# BLDC_DRIVER_REUSEPhase.net
KiCad netlist of a schematic drawn in EasyEDA Pro
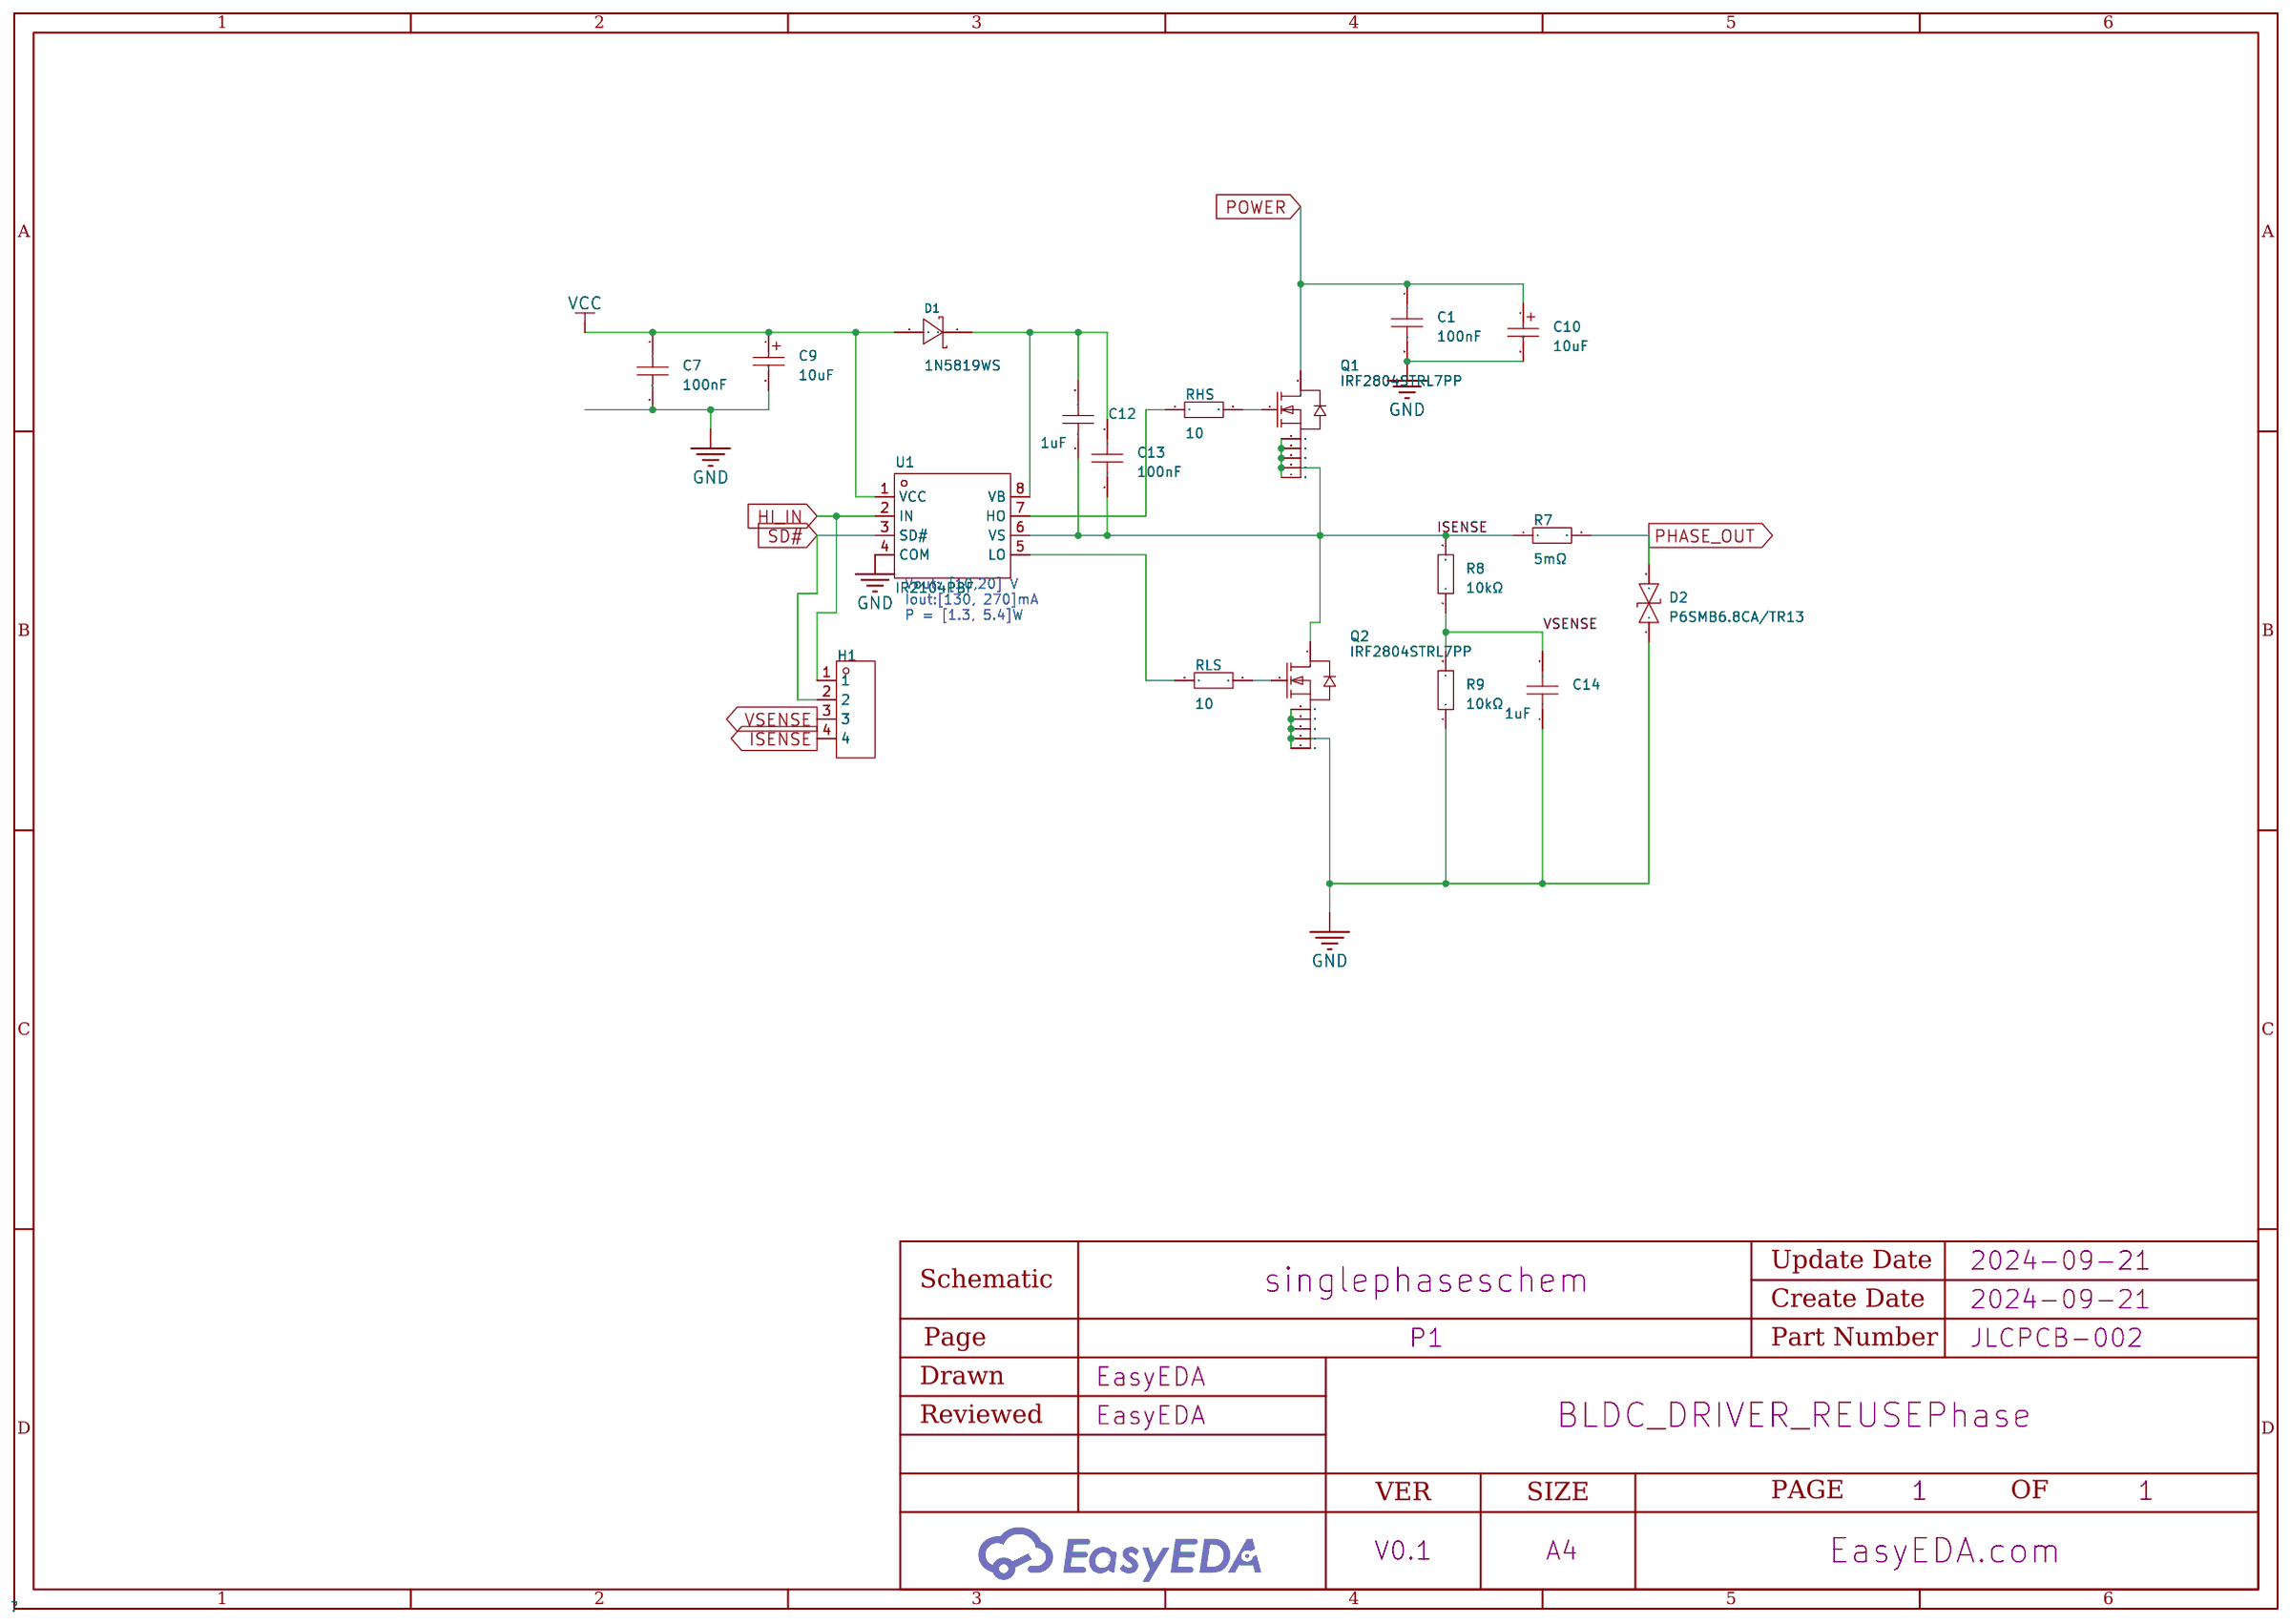
[diagram p0: schematic sheet]

(export (version "E")
  (design (tool "Eeschema 10.0.6"))
  (components
    (comp (ref "C1")
      (value "100nF")
      (footprint "easyedapro:C0603")
      (libsource (lib "easyedapro") (part "CAP"))
    )
    (comp (ref "C7")
      (value "100nF")
      (footprint "easyedapro:C0603")
      (libsource (lib "easyedapro") (part "CAP"))
    )
    (comp (ref "C9")
      (value "10uF")
      (footprint "easyedapro:CAP-SMD_BD5.0-L5.3-W5.3-LS6.3-FD")
      (libsource (lib "easyedapro") (part "C_Ele_SMD"))
    )
    (comp (ref "C10")
      (value "10uF")
      (footprint "easyedapro:CAP-SMD_BD5.0-L5.3-W5.3-LS6.3-FD")
      (libsource (lib "easyedapro") (part "C_Ele_SMD"))
    )
    (comp (ref "C12")
      (value "1uF")
      (footprint "easyedapro:CAP-TH_L7.2-W2.5-P5.00-D0.6")
      (fields (field (name "Manufacturer Part") "SMEC334J100M2") (field (name "Manufacturer") "CHAMPION(全鹏)"))
      (libsource (lib "easyedapro") (part "SMEC334J100M2"))
    )
    (comp (ref "C13")
      (value "100nF")
      (footprint "easyedapro:C0603")
      (libsource (lib "easyedapro") (part "CAP"))
    )
    (comp (ref "C14")
      (value "1uF")
      (footprint "easyedapro:CAP-TH_L7.2-W2.5-P5.00-D0.6")
      (fields (field (name "Manufacturer Part") "SMEC334J100M2") (field (name "Manufacturer") "CHAMPION(全鹏)"))
      (libsource (lib "easyedapro") (part "SMEC334J100M2"))
    )
    (comp (ref "D1")
      (value "1N5819WS")
      (footprint "easyedapro:SOD-323_L1.8-W1.3-LS2.5-RD")
      (description "Forward Voltage (Vf@If):600mV@1A Reverse Voltage (Vr):40V Average Rectified Current (Io):1A")
      (fields (field (name "Manufacturer") "Hottech(合科泰)"))
      (libsource (lib "easyedapro") (part "1N5819WS"))
    )
    (comp (ref "D2")
      (value "P6SMB6.8CA/TR13")
      (footprint "easyedapro:SMB_L4.6-W3.6-LS5.3-BI")
      (fields (field (name "Manufacturer") "Brightking(君耀电子)"))
      (libsource (lib "easyedapro") (part "P6SMB6.8CA-C78395"))
    )
    (comp (ref "H1")
      (value "~")
      (footprint "easyedapro:HDR-TH_4P-P2.54-V-M")
      (libsource (lib "easyedapro") (part "PZ254V-11-04P"))
    )
    (comp (ref "Q1")
      (value "IRF2804STRL7PP")
      (footprint "easyedapro:D2PAK-7_L10.6-W9.6-P1.27-LS15.9-BR")
      (fields (field (name "Manufacturer") "Infineon(英飞凌)"))
      (libsource (lib "easyedapro") (part "IRF2804STRL7PP"))
    )
    (comp (ref "Q2")
      (value "IRF2804STRL7PP")
      (footprint "easyedapro:D2PAK-7_L10.6-W9.6-P1.27-LS15.9-BR")
      (fields (field (name "Manufacturer") "Infineon(英飞凌)"))
      (libsource (lib "easyedapro") (part "IRF2804STRL7PP"))
    )
    (comp (ref "R7")
      (value "5mΩ")
      (footprint "easyedapro:R2512")
      (fields
        (field (name "Manufacturer Part") "PA2512FKF7W0R005E")
        (field (name "Manufacturer") "YAGEO(国巨)")
      )
      (libsource (lib "easyedapro") (part "PA2512FKF7W0R005L"))
    )
    (comp (ref "R8")
      (value "10kΩ")
      (footprint "easyedapro:R1210")
      (libsource (lib "easyedapro") (part "Res"))
    )
    (comp (ref "R9")
      (value "10kΩ")
      (footprint "easyedapro:R1210")
      (libsource (lib "easyedapro") (part "Res"))
    )
    (comp (ref "RHS") (value "10") (footprint "easyedapro:R1210") (libsource (lib "easyedapro") (part "Res")))
    (comp (ref "RLS") (value "10") (footprint "easyedapro:R1210") (libsource (lib "easyedapro") (part "Res")))
    (comp (ref "U1")
      (value "IR2104PBF")
      (footprint "easyedapro:DIP-8_L9.9-W6.6-P2.54-LS7.62-BL")
      (fields (field (name "Manufacturer") "Infineon(英飞凌)"))
      (libsource (lib "easyedapro") (part "IR2104PBF"))
    )
  )
  (nets
    (net (code "1") (name "GND") (class "Default")
      (node (ref "C1") (pin "2") (pinfunction "2_2") (pintype "input"))
      (node (ref "C10") (pin "2") (pinfunction "2_2") (pintype "input"))
      (node (ref "C14") (pin "1") (pinfunction "1_1") (pintype "input"))
      (node (ref "C7") (pin "2") (pinfunction "2_2") (pintype "input"))
      (node (ref "C9") (pin "2") (pinfunction "2_2") (pintype "input"))
      (node (ref "D2") (pin "1") (pinfunction "1_1") (pintype "unspecified"))
      (node (ref "Q2") (pin "2") (pinfunction "S_2") (pintype "unspecified"))
      (node (ref "Q2") (pin "3") (pinfunction "S_3") (pintype "unspecified"))
      (node (ref "Q2") (pin "5") (pinfunction "S_5") (pintype "unspecified"))
      (node (ref "Q2") (pin "6") (pinfunction "S_6") (pintype "unspecified"))
      (node (ref "Q2") (pin "7") (pinfunction "S_7") (pintype "unspecified"))
      (node (ref "R9") (pin "1") (pinfunction "1_1") (pintype "input"))
      (node (ref "U1") (pin "4") (pinfunction "COM_4") (pintype "unspecified"))
    )
    (net (code "2") (name "HI_IN") (class "Default")
      (node (ref "H1") (pin "1") (pinfunction "1_1") (pintype "unspecified"))
      (node (ref "U1") (pin "2") (pinfunction "IN_2") (pintype "unspecified"))
    )
    (net (code "3") (name "ISENSE") (class "Default")
      (node (ref "C12") (pin "1") (pinfunction "1_1") (pintype "input"))
      (node (ref "C13") (pin "2") (pinfunction "2_2") (pintype "input"))
      (node (ref "H1") (pin "4") (pinfunction "4_4") (pintype "unspecified"))
      (node (ref "Q1") (pin "2") (pinfunction "S_2") (pintype "unspecified"))
      (node (ref "Q1") (pin "3") (pinfunction "S_3") (pintype "unspecified"))
      (node (ref "Q1") (pin "5") (pinfunction "S_5") (pintype "unspecified"))
      (node (ref "Q1") (pin "6") (pinfunction "S_6") (pintype "unspecified"))
      (node (ref "Q1") (pin "7") (pinfunction "S_7") (pintype "unspecified"))
      (node (ref "Q2") (pin "4") (pinfunction "D_4") (pintype "unspecified"))
      (node (ref "R7") (pin "1") (pinfunction "1_1") (pintype "unspecified"))
      (node (ref "R8") (pin "2") (pinfunction "2_2") (pintype "input"))
      (node (ref "U1") (pin "6") (pinfunction "VS_6") (pintype "unspecified"))
    )
    (net (code "4") (name "Net-(D1-K)") (class "Default")
      (node (ref "C12") (pin "2") (pinfunction "2_2") (pintype "input"))
      (node (ref "C13") (pin "1") (pinfunction "1_1") (pintype "input"))
      (node (ref "D1") (pin "1") (pinfunction "K_1") (pintype "input"))
      (node (ref "U1") (pin "8") (pinfunction "VB_8") (pintype "unspecified"))
    )
    (net (code "5") (name "Net-(Q1-G)") (class "Default")
      (node (ref "Q1") (pin "1") (pinfunction "G_1") (pintype "unspecified"))
      (node (ref "RHS") (pin "2") (pinfunction "2_2") (pintype "input"))
    )
    (net (code "6") (name "Net-(Q2-G)") (class "Default")
      (node (ref "Q2") (pin "1") (pinfunction "G_1") (pintype "unspecified"))
      (node (ref "RLS") (pin "2") (pinfunction "2_2") (pintype "input"))
    )
    (net (code "7") (name "Net-(U1-HO)") (class "Default")
      (node (ref "RHS") (pin "1") (pinfunction "1_1") (pintype "input"))
      (node (ref "U1") (pin "7") (pinfunction "HO_7") (pintype "unspecified"))
    )
    (net (code "8") (name "Net-(U1-LO)") (class "Default")
      (node (ref "RLS") (pin "1") (pinfunction "1_1") (pintype "input"))
      (node (ref "U1") (pin "5") (pinfunction "LO_5") (pintype "unspecified"))
    )
    (net (code "9") (name "PHASE_OUT") (class "Default")
      (node (ref "D2") (pin "2") (pinfunction "2_2") (pintype "unspecified"))
      (node (ref "R7") (pin "2") (pinfunction "2_2") (pintype "unspecified"))
    )
    (net (code "10") (name "POWER") (class "Default")
      (node (ref "C1") (pin "1") (pinfunction "1_1") (pintype "input"))
      (node (ref "C10") (pin "1") (pinfunction "1_1") (pintype "input"))
      (node (ref "Q1") (pin "4") (pinfunction "D_4") (pintype "unspecified"))
    )
    (net (code "11") (name "SD#") (class "Default")
      (node (ref "H1") (pin "2") (pinfunction "2_2") (pintype "unspecified"))
      (node (ref "U1") (pin "3") (pinfunction "SD#_3") (pintype "unspecified"))
    )
    (net (code "12") (name "VCC") (class "Default")
      (node (ref "C7") (pin "1") (pinfunction "1_1") (pintype "input"))
      (node (ref "C9") (pin "1") (pinfunction "1_1") (pintype "input"))
      (node (ref "D1") (pin "2") (pinfunction "A_2") (pintype "input"))
      (node (ref "U1") (pin "1") (pinfunction "VCC_1") (pintype "unspecified"))
    )
    (net (code "13") (name "VSENSE") (class "Default")
      (node (ref "C14") (pin "2") (pinfunction "2_2") (pintype "input"))
      (node (ref "H1") (pin "3") (pinfunction "3_3") (pintype "unspecified"))
      (node (ref "R8") (pin "1") (pinfunction "1_1") (pintype "input"))
      (node (ref "R9") (pin "2") (pinfunction "2_2") (pintype "input"))
    )
  )
)
